# WaterProbe_TopConnector.net
KiCad netlist of a schematic drawn in EAGLE
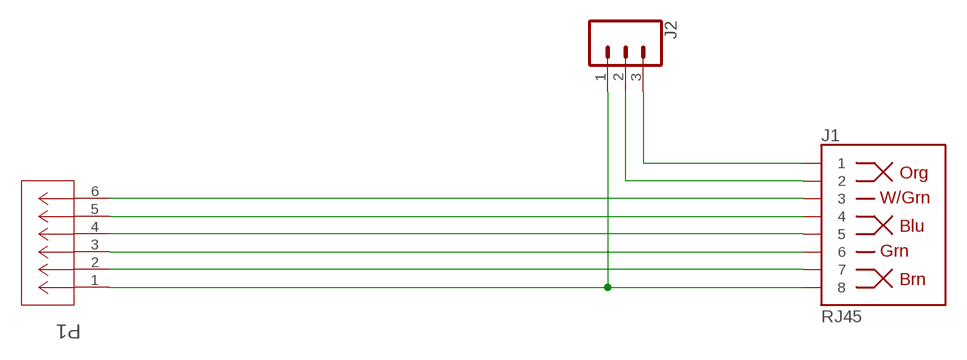
[diagram p0: schematic, sheet 1]

(export (version "E")
  (design (tool "Eeschema 10.0.6"))
  (components
    (comp (ref "J1")
      (value "RJ45")
      (footprint "eagle-import:RJ45-8")
      (libsource (lib "eagle-import") (part "RJ45-8"))
    )
    (comp (ref "J2")
      (value "CONN_03")
      (footprint "eagle-import:1X03")
      (libsource (lib "eagle-import") (part "CONN_03"))
    )
    (comp (ref "P1")
      (value "6PINJSTS6B-ZR(LF)(SN)")
      (footprint "eagle-import:S6B-ZR")
      (fields (field (name "MANUFACTURER_PART_NUMBER") "S6BZRLFSN"))
      (libsource (lib "eagle-import") (part "6PINJSTS6B-ZR(LF)(SN)"))
    )
  )
  (nets
    (net (code "1") (name "Net-(J1-Pad1)") (class "Default")
      (node (ref "J1") (pin "1") (pinfunction "1_1") (pintype "bidirectional"))
      (node (ref "J2") (pin "3") (pinfunction "3_3") (pintype "passive"))
    )
    (net (code "2") (name "Net-(J1-Pad2)") (class "Default")
      (node (ref "J1") (pin "2") (pinfunction "2_2") (pintype "bidirectional"))
      (node (ref "J2") (pin "2") (pinfunction "2_2") (pintype "passive"))
    )
    (net (code "3") (name "Net-(J1-Pad3)") (class "Default")
      (node (ref "J1") (pin "3") (pinfunction "3_3") (pintype "bidirectional"))
      (node (ref "P1") (pin "6") (pinfunction "6_6") (pintype "passive"))
    )
    (net (code "4") (name "Net-(J1-Pad4)") (class "Default")
      (node (ref "J1") (pin "4") (pinfunction "4_4") (pintype "bidirectional"))
      (node (ref "P1") (pin "5") (pinfunction "5_5") (pintype "passive"))
    )
    (net (code "5") (name "Net-(J1-Pad5)") (class "Default")
      (node (ref "J1") (pin "5") (pinfunction "5_5") (pintype "bidirectional"))
      (node (ref "P1") (pin "4") (pinfunction "4_4") (pintype "passive"))
    )
    (net (code "6") (name "Net-(J1-Pad6)") (class "Default")
      (node (ref "J1") (pin "6") (pinfunction "6_6") (pintype "bidirectional"))
      (node (ref "P1") (pin "3") (pinfunction "3_3") (pintype "passive"))
    )
    (net (code "7") (name "Net-(J1-Pad7)") (class "Default")
      (node (ref "J1") (pin "7") (pinfunction "7_7") (pintype "bidirectional"))
      (node (ref "P1") (pin "2") (pinfunction "2_2") (pintype "passive"))
    )
    (net (code "8") (name "Net-(J1-Pad8)") (class "Default")
      (node (ref "J1") (pin "8") (pinfunction "8_8") (pintype "bidirectional"))
      (node (ref "J2") (pin "1") (pinfunction "1_1") (pintype "passive"))
      (node (ref "P1") (pin "1") (pinfunction "1_1") (pintype "passive"))
    )
  )
)
